# rbl.net
KiCad netlist of a schematic drawn in Altium Designer
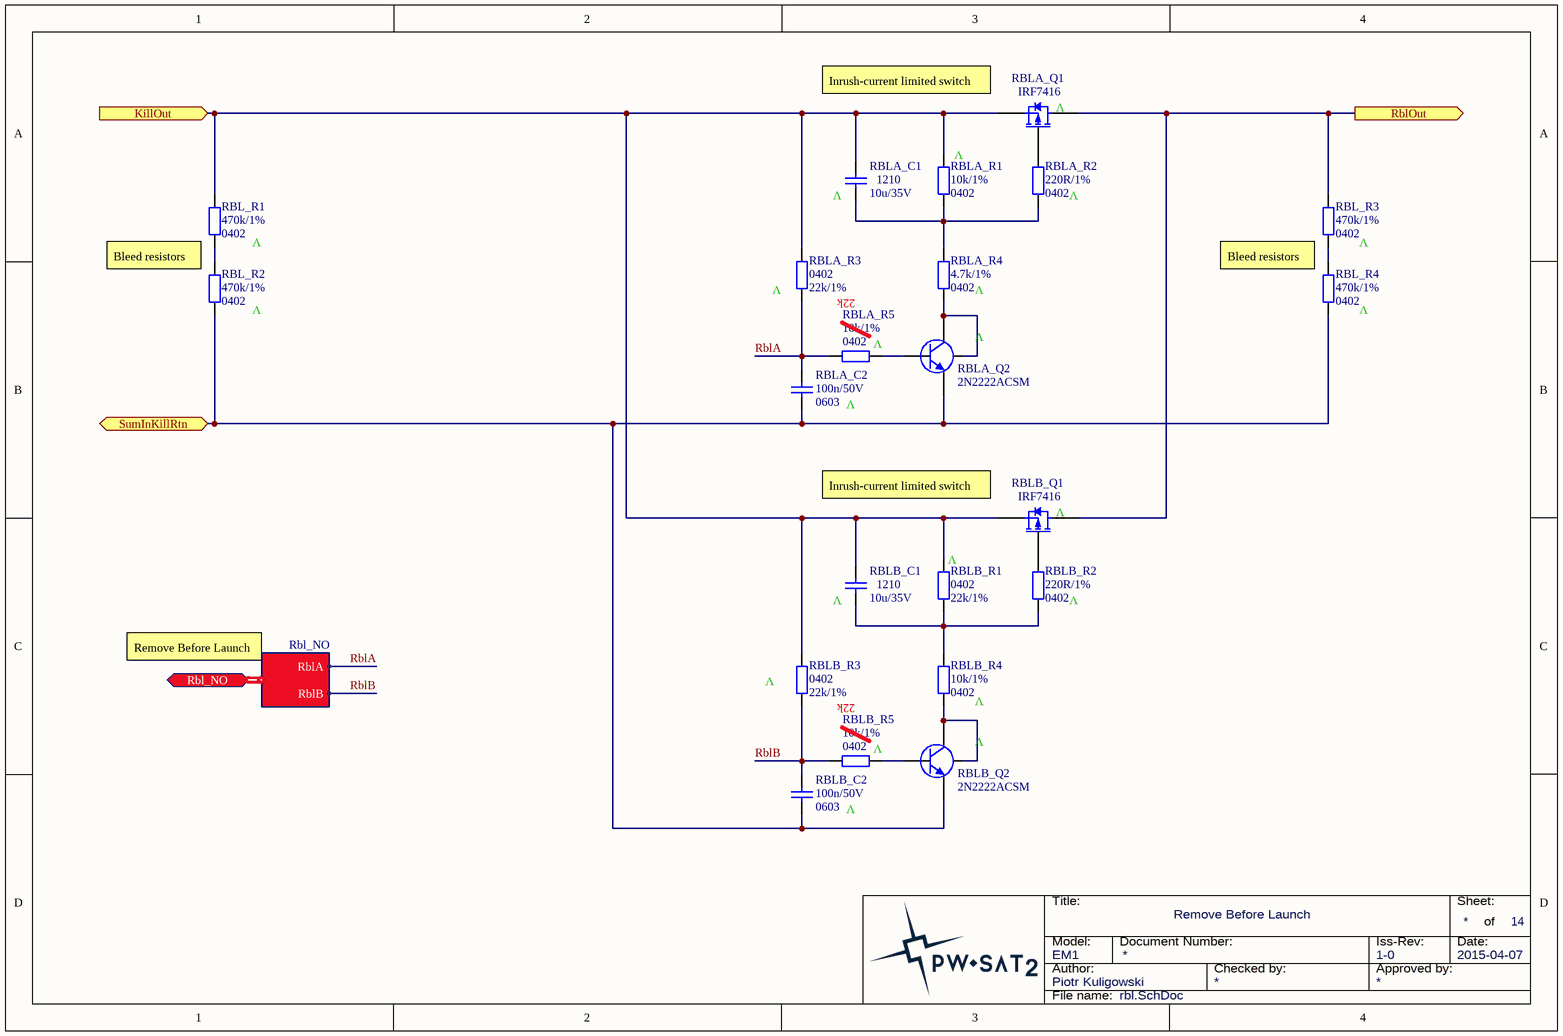
[diagram p0: rbl.SchDoc]

(export (version "E")
  (design (tool "Eeschema 10.0.6"))
  (components
    (comp (ref "RBLA_C1")
      (value "10u/35V")
      (footprint "SMD_Capacitor_1210")
      (description "Ceramic Cap Murata Automotive 10u/35V X7S 1210")
      (fields
        (field (name "MANUFACTURER") "Murata")
        (field (name "MANUFACTURERPARTNUMBER") "GCM32EC7YA106KA03K")
        (field (name "PACKAGE") "1210")
      )
      (libsource (lib "capacitors") (part "Cer_GCM32EC7YA106KA03K"))
    )
    (comp (ref "RBLA_C2")
      (value "100n/50V")
      (footprint "SMD_Capacitor_0603")
      (description "Ceramic Cap Murata Automotive 100n/50V X7R 0603")
      (fields
        (field (name "MANUFACTURER") "Murata")
        (field (name "MANUFACTURERPARTNUMBER") "GCJ188R71H104KA12D")
        (field (name "PACKAGE") "0603")
      )
      (libsource (lib "capacitors") (part "Cer_GCJ188R71H104KA12D"))
    )
    (comp (ref "RBLA_Q1")
      (value "IRF7416")
      (footprint "SOIC-8-N_SSSGDDDD")
      (description "10A/30V HEXFET Power P-MOSFET.")
      (fields (field (name "MANUFACTURER") "International Rectifier"))
      (libsource (lib "transistors") (part "IRF7416"))
    )
    (comp (ref "RBLA_Q2")
      (value "2N2222ACSM")
      (footprint "LCC1-4_BEC")
      (description "Silicon Planar Epitaxial NPN Transistor.")
      (fields (field (name "MANUFACTURER") "Semelab-TT"))
      (libsource (lib "transistors") (part "2N2222ACSM"))
    )
    (comp (ref "RBLA_R1")
      (value "10k/1%")
      (footprint "SMD_Resistor_0402")
      (description "10k/1% Vishay CRCW 0402 Resistor. 63mW, 100ppm, 50V.")
      (fields
        (field (name "MANUFACTURER") "Vishay")
        (field (name "MANUFACTURERPARTNUMBER") "CRCW040210K0FKxxxx")
        (field (name "PACKAGE") "0402")
      )
      (libsource (lib "resistors") (part "CRCW040210K0FKxxxx"))
    )
    (comp (ref "RBLA_R2")
      (value "220R/1%")
      (footprint "SMD_Resistor_0402")
      (description "220R/1% Vishay CRCW 0402 Resistor. 63mW, 100ppm, 50V.")
      (fields
        (field (name "MANUFACTURER") "Vishay")
        (field (name "MANUFACTURERPARTNUMBER") "CRCW0402220RFKxxxx")
        (field (name "PACKAGE") "0402")
      )
      (libsource (lib "resistors") (part "CRCW0402220RFKxxxx"))
    )
    (comp (ref "RBLA_R3")
      (value "22k/1%")
      (footprint "SMD_Resistor_0402")
      (description "22k/1% Vishay CRCW 0402 Resistor. 63mW, 100ppm, 50V.")
      (fields
        (field (name "MANUFACTURER") "Vishay")
        (field (name "MANUFACTURERPARTNUMBER") "CRCW040222K0FKxxxx")
        (field (name "PACKAGE") "0402")
      )
      (libsource (lib "resistors") (part "CRCW040222K0FKxxxx"))
    )
    (comp (ref "RBLA_R4")
      (value "4.7k/1%")
      (footprint "SMD_Resistor_0402")
      (description "4.7k/1% Vishay CRCW 0402 Resistor. 63mW, 100ppm, 50V.")
      (fields
        (field (name "MANUFACTURERPARTNUMBER") "CRCW04024K70FKxxxx")
        (field (name "MANUFACTURER") "Vishay")
        (field (name "PACKAGE") "0402")
      )
      (libsource (lib "resistors") (part "CRCW04024K70FKxxxx"))
    )
    (comp (ref "RBLA_R5")
      (value "10k/1%")
      (footprint "SMD_Resistor_0402")
      (description "10k/1% Vishay CRCW 0402 Resistor. 63mW, 100ppm, 50V.")
      (fields
        (field (name "MANUFACTURER") "Vishay")
        (field (name "MANUFACTURERPARTNUMBER") "CRCW040210K0FKxxxx")
        (field (name "PACKAGE") "0402")
      )
      (libsource (lib "") (part "CRCW040210K0FKxxxx_1"))
    )
    (comp (ref "RBLB_C1")
      (value "10u/35V")
      (footprint "SMD_Capacitor_1210")
      (description "Ceramic Cap Murata Automotive 10u/35V X7S 1210")
      (fields
        (field (name "MANUFACTURER") "Murata")
        (field (name "MANUFACTURERPARTNUMBER") "GCM32EC7YA106KA03K")
        (field (name "PACKAGE") "1210")
      )
      (libsource (lib "capacitors") (part "Cer_GCM32EC7YA106KA03K"))
    )
    (comp (ref "RBLB_C2")
      (value "100n/50V")
      (footprint "SMD_Capacitor_0603")
      (description "Ceramic Cap Murata Automotive 100n/50V X7R 0603")
      (fields
        (field (name "MANUFACTURER") "Murata")
        (field (name "MANUFACTURERPARTNUMBER") "GCJ188R71H104KA12D")
        (field (name "PACKAGE") "0603")
      )
      (libsource (lib "capacitors") (part "Cer_GCJ188R71H104KA12D"))
    )
    (comp (ref "RBLB_Q1")
      (value "IRF7416")
      (footprint "SOIC-8-N_SSSGDDDD")
      (description "10A/30V HEXFET Power P-MOSFET.")
      (fields (field (name "MANUFACTURER") "International Rectifier"))
      (libsource (lib "transistors") (part "IRF7416"))
    )
    (comp (ref "RBLB_Q2")
      (value "2N2222ACSM")
      (footprint "LCC1-4_BEC")
      (description "Silicon Planar Epitaxial NPN Transistor.")
      (fields (field (name "MANUFACTURER") "Semelab-TT"))
      (libsource (lib "transistors") (part "2N2222ACSM"))
    )
    (comp (ref "RBLB_R1")
      (value "22k/1%")
      (footprint "SMD_Resistor_0402")
      (description "22k/1% Vishay CRCW 0402 Resistor. 63mW, 100ppm, 50V.")
      (fields
        (field (name "MANUFACTURER") "Vishay")
        (field (name "MANUFACTURERPARTNUMBER") "CRCW040222K0FKxxxx")
        (field (name "PACKAGE") "0402")
      )
      (libsource (lib "resistors") (part "CRCW040222K0FKxxxx"))
    )
    (comp (ref "RBLB_R2")
      (value "220R/1%")
      (footprint "SMD_Resistor_0402")
      (description "220R/1% Vishay CRCW 0402 Resistor. 63mW, 100ppm, 50V.")
      (fields
        (field (name "MANUFACTURER") "Vishay")
        (field (name "MANUFACTURERPARTNUMBER") "CRCW0402220RFKxxxx")
        (field (name "PACKAGE") "0402")
      )
      (libsource (lib "resistors") (part "CRCW0402220RFKxxxx"))
    )
    (comp (ref "RBLB_R3")
      (value "22k/1%")
      (footprint "SMD_Resistor_0402")
      (description "22k/1% Vishay CRCW 0402 Resistor. 63mW, 100ppm, 50V.")
      (fields
        (field (name "MANUFACTURER") "Vishay")
        (field (name "MANUFACTURERPARTNUMBER") "CRCW040222K0FKxxxx")
        (field (name "PACKAGE") "0402")
      )
      (libsource (lib "resistors") (part "CRCW040222K0FKxxxx"))
    )
    (comp (ref "RBLB_R4")
      (value "10k/1%")
      (footprint "SMD_Resistor_0402")
      (description "10k/1% Vishay CRCW 0402 Resistor. 63mW, 100ppm, 50V.")
      (fields
        (field (name "MANUFACTURER") "Vishay")
        (field (name "MANUFACTURERPARTNUMBER") "CRCW040210K0FKxxxx")
        (field (name "PACKAGE") "0402")
      )
      (libsource (lib "resistors") (part "CRCW040210K0FKxxxx"))
    )
    (comp (ref "RBLB_R5")
      (value "10k/1%")
      (footprint "SMD_Resistor_0402")
      (description "10k/1% Vishay CRCW 0402 Resistor. 63mW, 100ppm, 50V.")
      (fields
        (field (name "MANUFACTURER") "Vishay")
        (field (name "MANUFACTURERPARTNUMBER") "CRCW040210K0FKxxxx")
        (field (name "PACKAGE") "0402")
      )
      (libsource (lib "") (part "CRCW040210K0FKxxxx_1"))
    )
    (comp (ref "RBL_R1")
      (value "470k/1%")
      (footprint "SMD_Resistor_0402")
      (description "470k/1% Vishay CRCW 0402 Resistor. 63mW, 100ppm, 50V.")
      (fields
        (field (name "MANUFACTURER") "Vishay")
        (field (name "MANUFACTURERPARTNUMBER") "CRCW0402470KFKxxxx")
        (field (name "PACKAGE") "0402")
      )
      (libsource (lib "resistors") (part "CRCW0402470KFKxxxx"))
    )
    (comp (ref "RBL_R2")
      (value "470k/1%")
      (footprint "SMD_Resistor_0402")
      (description "470k/1% Vishay CRCW 0402 Resistor. 63mW, 100ppm, 50V.")
      (fields
        (field (name "MANUFACTURER") "Vishay")
        (field (name "MANUFACTURERPARTNUMBER") "CRCW0402470KFKxxxx")
        (field (name "PACKAGE") "0402")
      )
      (libsource (lib "resistors") (part "CRCW0402470KFKxxxx"))
    )
    (comp (ref "RBL_R3")
      (value "470k/1%")
      (footprint "SMD_Resistor_0402")
      (description "470k/1% Vishay CRCW 0402 Resistor. 63mW, 100ppm, 50V.")
      (fields
        (field (name "MANUFACTURER") "Vishay")
        (field (name "MANUFACTURERPARTNUMBER") "CRCW0402470KFKxxxx")
        (field (name "PACKAGE") "0402")
      )
      (libsource (lib "resistors") (part "CRCW0402470KFKxxxx"))
    )
    (comp (ref "RBL_R4")
      (value "470k/1%")
      (footprint "SMD_Resistor_0402")
      (description "470k/1% Vishay CRCW 0402 Resistor. 63mW, 100ppm, 50V.")
      (fields
        (field (name "MANUFACTURER") "Vishay")
        (field (name "MANUFACTURERPARTNUMBER") "CRCW0402470KFKxxxx")
        (field (name "PACKAGE") "0402")
      )
      (libsource (lib "resistors") (part "CRCW0402470KFKxxxx"))
    )
  )
  (nets
    (net (code "2") (name "/KillOut") (class "Default")
      (node (ref "RBLA_C1") (pin "1") (pinfunction "1_1") (pintype "passive"))
      (node (ref "RBLA_Q1") (pin "S") (pinfunction "S_S") (pintype "passive"))
      (node (ref "RBLA_R1") (pin "1") (pinfunction "1_1") (pintype "passive"))
      (node (ref "RBLA_R3") (pin "1") (pinfunction "1_1") (pintype "passive"))
      (node (ref "RBLB_C1") (pin "1") (pinfunction "1_1") (pintype "passive"))
      (node (ref "RBLB_Q1") (pin "S") (pinfunction "S_S") (pintype "passive"))
      (node (ref "RBLB_R1") (pin "1") (pinfunction "1_1") (pintype "passive"))
      (node (ref "RBLB_R3") (pin "1") (pinfunction "1_1") (pintype "passive"))
      (node (ref "RBL_R1") (pin "1") (pinfunction "1_1") (pintype "passive"))
    )
    (net (code "3") (name "/RblA") (class "Default")
      (node (ref "RBLA_C2") (pin "1") (pinfunction "1_1") (pintype "passive"))
      (node (ref "RBLA_R3") (pin "2") (pinfunction "2_2") (pintype "passive"))
      (node (ref "RBLA_R5") (pin "1") (pinfunction "1_1") (pintype "passive"))
    )
    (net (code "4") (name "/RblB") (class "Default")
      (node (ref "RBLB_C2") (pin "1") (pinfunction "1_1") (pintype "passive"))
      (node (ref "RBLB_R3") (pin "2") (pinfunction "2_2") (pintype "passive"))
      (node (ref "RBLB_R5") (pin "1") (pinfunction "1_1") (pintype "passive"))
    )
    (net (code "5") (name "/RblOut") (class "Default")
      (node (ref "RBLA_Q1") (pin "D") (pinfunction "D_D") (pintype "passive"))
      (node (ref "RBLB_Q1") (pin "D") (pinfunction "D_D") (pintype "passive"))
      (node (ref "RBL_R3") (pin "1") (pinfunction "1_1") (pintype "passive"))
    )
    (net (code "6") (name "/SumInKillRtn") (class "Default")
      (node (ref "RBLA_C2") (pin "2") (pinfunction "2_2") (pintype "passive"))
      (node (ref "RBLA_Q2") (pin "E") (pinfunction "E_E") (pintype "passive"))
      (node (ref "RBLB_C2") (pin "2") (pinfunction "2_2") (pintype "passive"))
      (node (ref "RBLB_Q2") (pin "E") (pinfunction "E_E") (pintype "passive"))
      (node (ref "RBL_R2") (pin "2") (pinfunction "2_2") (pintype "passive"))
      (node (ref "RBL_R4") (pin "2") (pinfunction "2_2") (pintype "passive"))
    )
    (net (code "8") (name "Net-(RBLA_C1-Pad2)") (class "Default")
      (node (ref "RBLA_C1") (pin "2") (pinfunction "2_2") (pintype "passive"))
      (node (ref "RBLA_R1") (pin "2") (pinfunction "2_2") (pintype "passive"))
      (node (ref "RBLA_R2") (pin "2") (pinfunction "2_2") (pintype "passive"))
      (node (ref "RBLA_R4") (pin "1") (pinfunction "1_1") (pintype "passive"))
    )
    (net (code "9") (name "Net-(RBLA_Q1-PadG)") (class "Default")
      (node (ref "RBLA_Q1") (pin "G") (pinfunction "G_G") (pintype "passive"))
      (node (ref "RBLA_R2") (pin "1") (pinfunction "1_1") (pintype "passive"))
    )
    (net (code "10") (name "Net-(RBLA_Q2-PadB)") (class "Default")
      (node (ref "RBLA_Q2") (pin "B") (pinfunction "B_B") (pintype "passive"))
      (node (ref "RBLA_R5") (pin "2") (pinfunction "2_2") (pintype "passive"))
    )
    (net (code "11") (name "Net-(RBLA_Q2-PadC)") (class "Default")
      (node (ref "RBLA_Q2") (pin "C") (pinfunction "C_C") (pintype "passive"))
      (node (ref "RBLA_Q2") (pin "Shield") (pinfunction "Shield_Shield") (pintype "passive"))
      (node (ref "RBLA_R4") (pin "2") (pinfunction "2_2") (pintype "passive"))
    )
    (net (code "12") (name "Net-(RBLB_C1-Pad2)") (class "Default")
      (node (ref "RBLB_C1") (pin "2") (pinfunction "2_2") (pintype "passive"))
      (node (ref "RBLB_R1") (pin "2") (pinfunction "2_2") (pintype "passive"))
      (node (ref "RBLB_R2") (pin "2") (pinfunction "2_2") (pintype "passive"))
      (node (ref "RBLB_R4") (pin "1") (pinfunction "1_1") (pintype "passive"))
    )
    (net (code "13") (name "Net-(RBLB_Q1-PadG)") (class "Default")
      (node (ref "RBLB_Q1") (pin "G") (pinfunction "G_G") (pintype "passive"))
      (node (ref "RBLB_R2") (pin "1") (pinfunction "1_1") (pintype "passive"))
    )
    (net (code "14") (name "Net-(RBLB_Q2-PadB)") (class "Default")
      (node (ref "RBLB_Q2") (pin "B") (pinfunction "B_B") (pintype "passive"))
      (node (ref "RBLB_R5") (pin "2") (pinfunction "2_2") (pintype "passive"))
    )
    (net (code "15") (name "Net-(RBLB_Q2-PadC)") (class "Default")
      (node (ref "RBLB_Q2") (pin "C") (pinfunction "C_C") (pintype "passive"))
      (node (ref "RBLB_Q2") (pin "Shield") (pinfunction "Shield_Shield") (pintype "passive"))
      (node (ref "RBLB_R4") (pin "2") (pinfunction "2_2") (pintype "passive"))
    )
    (net (code "16") (name "Net-(RBL_R1-Pad2)") (class "Default")
      (node (ref "RBL_R1") (pin "2") (pinfunction "2_2") (pintype "passive"))
      (node (ref "RBL_R2") (pin "1") (pinfunction "1_1") (pintype "passive"))
    )
    (net (code "17") (name "Net-(RBL_R3-Pad2)") (class "Default")
      (node (ref "RBL_R3") (pin "2") (pinfunction "2_2") (pintype "passive"))
      (node (ref "RBL_R4") (pin "1") (pinfunction "1_1") (pintype "passive"))
    )
  )
)
